# Capacitive_Moisture_Sensor_REV_02.net
KiCad netlist of a schematic drawn in EAGLE
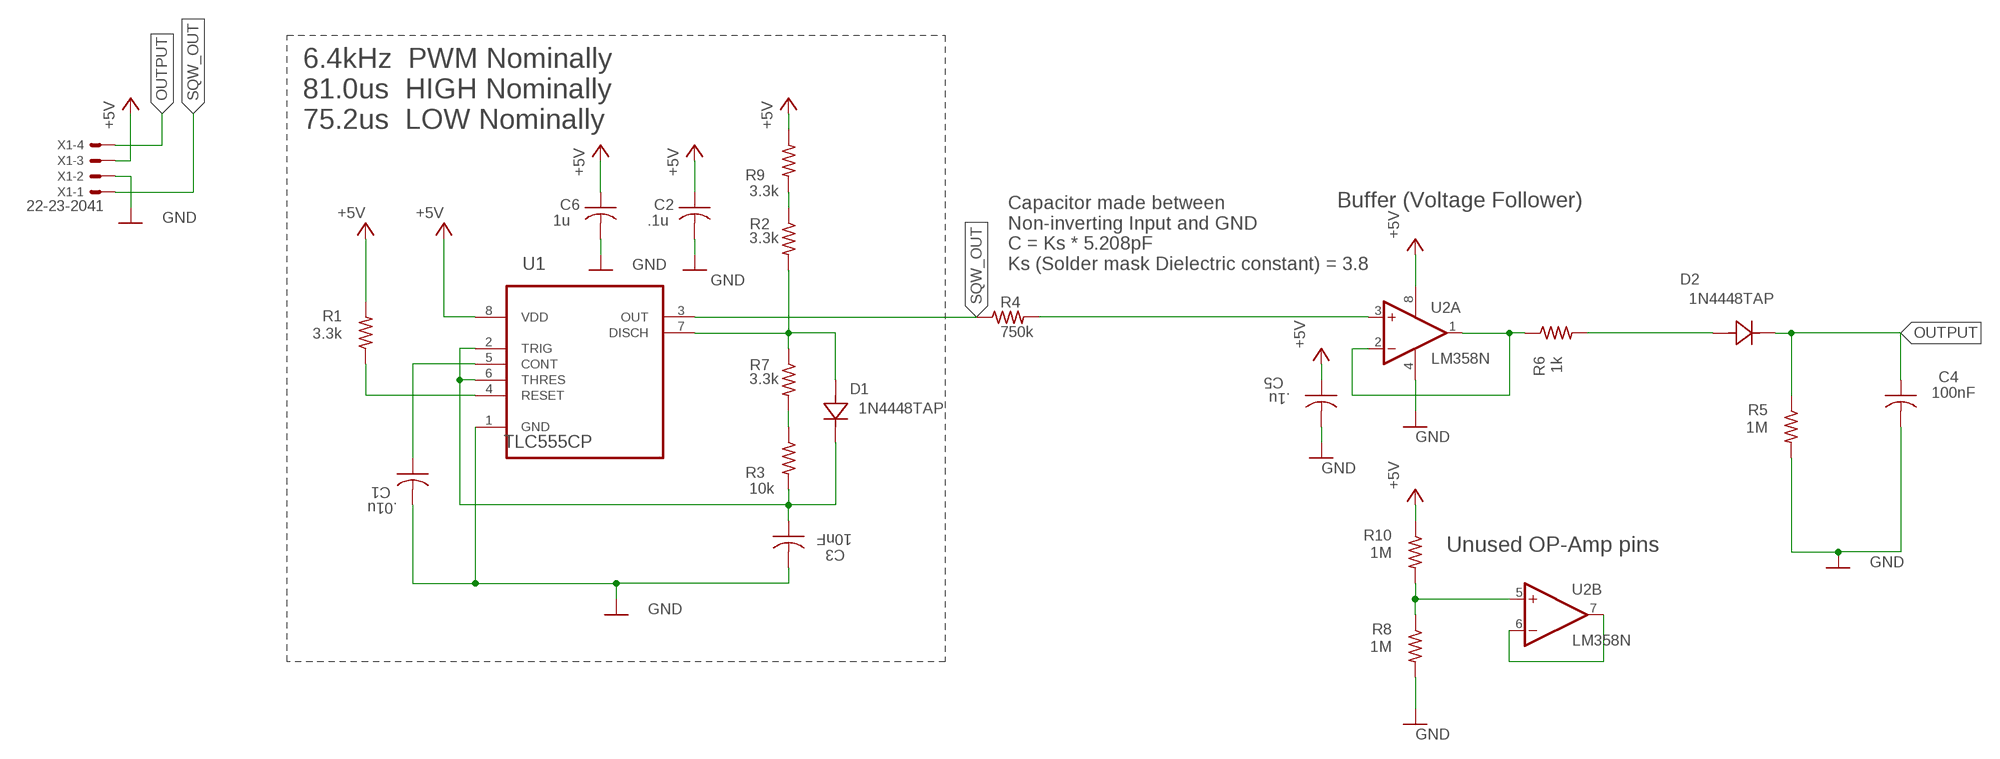
[diagram p0: schematic, sheet 1]

(export (version "E")
  (design (tool "Eeschema 10.0.6"))
  (components
    (comp (ref "C1")
      (value ".01u")
      (footprint "eagle-import:C1206")
      (libsource (lib "eagle-import") (part "C-USC1206"))
    )
    (comp (ref "C2")
      (value ".1u")
      (footprint "eagle-import:C1206")
      (libsource (lib "eagle-import") (part "C-USC1206"))
    )
    (comp (ref "C3")
      (value "10nF")
      (footprint "eagle-import:C1206")
      (libsource (lib "eagle-import") (part "C-USC1206"))
    )
    (comp (ref "C4")
      (value "100nF")
      (footprint "eagle-import:C1206")
      (libsource (lib "eagle-import") (part "C-USC1206"))
    )
    (comp (ref "C5")
      (value ".1u")
      (footprint "eagle-import:C1206")
      (libsource (lib "eagle-import") (part "C-USC1206"))
    )
    (comp (ref "C6")
      (value "1u")
      (footprint "eagle-import:C1206")
      (libsource (lib "eagle-import") (part "C-USC1206"))
    )
    (comp (ref "D1")
      (value "1N4448TAP")
      (footprint "eagle-import:DO-35")
      (libsource (lib "eagle-import") (part "1N4448TAP"))
    )
    (comp (ref "D2")
      (value "1N4448TAP")
      (footprint "eagle-import:DO-35")
      (libsource (lib "eagle-import") (part "1N4448TAP"))
    )
    (comp (ref "R1")
      (value "3.3k")
      (footprint "eagle-import:R1206")
      (libsource (lib "eagle-import") (part "R-US_R1206"))
    )
    (comp (ref "R2")
      (value "3.3k")
      (footprint "eagle-import:R1206")
      (libsource (lib "eagle-import") (part "R-US_R1206"))
    )
    (comp (ref "R3")
      (value "10k")
      (footprint "eagle-import:R1206")
      (libsource (lib "eagle-import") (part "R-US_R1206"))
    )
    (comp (ref "R4")
      (value "750k")
      (footprint "eagle-import:R1206")
      (libsource (lib "eagle-import") (part "R-US_R1206"))
    )
    (comp (ref "R5")
      (value "1M")
      (footprint "eagle-import:R1206")
      (libsource (lib "eagle-import") (part "R-US_R1206"))
    )
    (comp (ref "R6")
      (value "1k")
      (footprint "eagle-import:R1206")
      (libsource (lib "eagle-import") (part "R-US_R1206"))
    )
    (comp (ref "R7")
      (value "3.3k")
      (footprint "eagle-import:R1206")
      (libsource (lib "eagle-import") (part "R-US_R1206"))
    )
    (comp (ref "R8")
      (value "1M")
      (footprint "eagle-import:R1206")
      (libsource (lib "eagle-import") (part "R-US_R1206"))
    )
    (comp (ref "R9")
      (value "3.3k")
      (footprint "eagle-import:R1206")
      (libsource (lib "eagle-import") (part "R-US_R1206"))
    )
    (comp (ref "R10")
      (value "1M")
      (footprint "eagle-import:R1206")
      (libsource (lib "eagle-import") (part "R-US_R1206"))
    )
    (comp (ref "U1")
      (value "TLC555CP")
      (footprint "eagle-import:DIP254P762X508-8")
      (fields (field (name "MF") "Texas Instruments"))
      (libsource (lib "eagle-import") (part "TLC555CP"))
    )
    (comp (ref "U2")
      (value "LM358N")
      (footprint "eagle-import:DIL08")
      (libsource (lib "eagle-import") (part "LM358N"))
    )
    (comp (ref "X1")
      (value "22-23-2041")
      (footprint "eagle-import:22-23-2041")
      (fields (field (name "MF") "MOLEX"))
      (libsource (lib "eagle-import") (part "22-23-2041"))
    )
  )
  (nets
    (net (code "1") (name "+5V") (class "Default")
      (node (ref "C2") (pin "1") (pinfunction "1_1") (pintype "passive"))
      (node (ref "C5") (pin "1") (pinfunction "1_1") (pintype "passive"))
      (node (ref "C6") (pin "1") (pinfunction "1_1") (pintype "passive"))
      (node (ref "R1") (pin "2") (pinfunction "2_2") (pintype "passive"))
      (node (ref "R10") (pin "1") (pinfunction "1_1") (pintype "passive"))
      (node (ref "R9") (pin "1") (pinfunction "1_1") (pintype "passive"))
      (node (ref "U1") (pin "8") (pinfunction "VDD_8") (pintype "power_in"))
      (node (ref "U2") (pin "8") (pinfunction "V+_8") (pintype "power_in"))
      (node (ref "X1") (pin "3") (pinfunction "S_3") (pintype "passive"))
    )
    (net (code "2") (name "GND") (class "Default")
      (node (ref "C1") (pin "2") (pinfunction "2_2") (pintype "passive"))
      (node (ref "C2") (pin "2") (pinfunction "2_2") (pintype "passive"))
      (node (ref "C3") (pin "2") (pinfunction "2_2") (pintype "passive"))
      (node (ref "C4") (pin "2") (pinfunction "2_2") (pintype "passive"))
      (node (ref "C5") (pin "2") (pinfunction "2_2") (pintype "passive"))
      (node (ref "C6") (pin "2") (pinfunction "2_2") (pintype "passive"))
      (node (ref "R5") (pin "2") (pinfunction "2_2") (pintype "passive"))
      (node (ref "R8") (pin "2") (pinfunction "2_2") (pintype "passive"))
      (node (ref "U1") (pin "1") (pinfunction "GND_1") (pintype "passive"))
      (node (ref "U2") (pin "4") (pinfunction "V-_4") (pintype "power_in"))
      (node (ref "X1") (pin "2") (pinfunction "S_2") (pintype "passive"))
    )
    (net (code "3") (name "Net-(D2-Pad2)") (class "Default")
      (node (ref "D2") (pin "2") (pinfunction "2_2") (pintype "passive"))
      (node (ref "R6") (pin "2") (pinfunction "2_2") (pintype "passive"))
    )
    (net (code "4") (name "Net-(R2-Pad1)") (class "Default")
      (node (ref "R2") (pin "1") (pinfunction "1_1") (pintype "passive"))
      (node (ref "R9") (pin "2") (pinfunction "2_2") (pintype "passive"))
    )
    (net (code "5") (name "Net-(R3-Pad1)") (class "Default")
      (node (ref "R3") (pin "1") (pinfunction "1_1") (pintype "passive"))
      (node (ref "R7") (pin "2") (pinfunction "2_2") (pintype "passive"))
    )
    (net (code "6") (name "Net-(U1-CONT)") (class "Default")
      (node (ref "C1") (pin "1") (pinfunction "1_1") (pintype "passive"))
      (node (ref "U1") (pin "5") (pinfunction "CONT_5") (pintype "input"))
    )
    (net (code "7") (name "Net-(U1-DISCH)") (class "Default")
      (node (ref "D1") (pin "2") (pinfunction "2_2") (pintype "passive"))
      (node (ref "R2") (pin "2") (pinfunction "2_2") (pintype "passive"))
      (node (ref "R7") (pin "1") (pinfunction "1_1") (pintype "passive"))
      (node (ref "U1") (pin "7") (pinfunction "DISCH_7") (pintype "output"))
    )
    (net (code "8") (name "Net-(U1-RESET)") (class "Default")
      (node (ref "R1") (pin "1") (pinfunction "1_1") (pintype "passive"))
      (node (ref "U1") (pin "4") (pinfunction "RESET_4") (pintype "input"))
    )
    (net (code "9") (name "Net-(U1-THRES)") (class "Default")
      (node (ref "C3") (pin "1") (pinfunction "1_1") (pintype "passive"))
      (node (ref "D1") (pin "1") (pinfunction "1_1") (pintype "passive"))
      (node (ref "R3") (pin "2") (pinfunction "2_2") (pintype "passive"))
      (node (ref "U1") (pin "2") (pinfunction "TRIG_2") (pintype "input"))
      (node (ref "U1") (pin "6") (pinfunction "THRES_6") (pintype "input"))
    )
    (net (code "10") (name "Net-(U2A-+IN)") (class "Default")
      (node (ref "R4") (pin "2") (pinfunction "2_2") (pintype "passive"))
      (node (ref "U2") (pin "3") (pinfunction "+IN_3") (pintype "input"))
    )
    (net (code "11") (name "Net-(U2A--IN)") (class "Default")
      (node (ref "R6") (pin "1") (pinfunction "1_1") (pintype "passive"))
      (node (ref "U2") (pin "1") (pinfunction "OUT_1") (pintype "output"))
      (node (ref "U2") (pin "2") (pinfunction "-IN_2") (pintype "input"))
    )
    (net (code "12") (name "Net-(U2B-+IN)") (class "Default")
      (node (ref "R10") (pin "2") (pinfunction "2_2") (pintype "passive"))
      (node (ref "R8") (pin "1") (pinfunction "1_1") (pintype "passive"))
      (node (ref "U2") (pin "5") (pinfunction "+IN_5") (pintype "input"))
    )
    (net (code "13") (name "Net-(U2B--IN)") (class "Default")
      (node (ref "U2") (pin "6") (pinfunction "-IN_6") (pintype "input"))
      (node (ref "U2") (pin "7") (pinfunction "OUT_7") (pintype "output"))
    )
    (net (code "14") (name "OUTPUT") (class "Default")
      (node (ref "C4") (pin "1") (pinfunction "1_1") (pintype "passive"))
      (node (ref "D2") (pin "1") (pinfunction "1_1") (pintype "passive"))
      (node (ref "R5") (pin "1") (pinfunction "1_1") (pintype "passive"))
      (node (ref "X1") (pin "4") (pinfunction "S_4") (pintype "passive"))
    )
    (net (code "15") (name "SQW_OUT") (class "Default")
      (node (ref "R4") (pin "1") (pinfunction "1_1") (pintype "passive"))
      (node (ref "U1") (pin "3") (pinfunction "OUT_3") (pintype "output"))
      (node (ref "X1") (pin "1") (pinfunction "S_1") (pintype "passive"))
    )
  )
)
